# Angle-Sensor_V1_0.net
KiCad netlist of a schematic drawn in Altium Designer
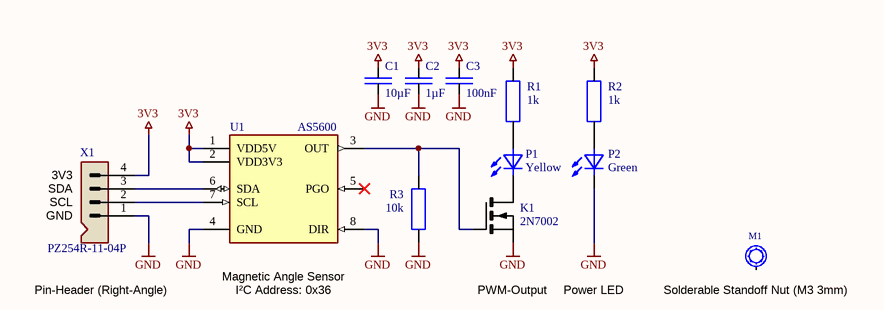
[diagram p0: Angle-Sensor_V1.0.SchDoc]

(export (version "E")
  (design (tool "Eeschema 10.0.6"))
  (components
    (comp (ref "C1")
      (value "10µF")
      (footprint "SMD Keramikkondensator 1206")
      (description "SMD Ceramic Capacitor E6")
      (libsource (lib "Ceramic Capacitors-E6") (part "E6 - 10uF"))
    )
    (comp (ref "C2")
      (value "1µF")
      (footprint "SMD Keramikkondensator 0603")
      (description "CAP-MK")
      (libsource (lib "AudioAmp") (part "C-CAPACITOR"))
    )
    (comp (ref "C3")
      (value "100nF")
      (footprint "SMD Keramikkondensator 0603")
      (description "SMD Ceramic Capacitor E6")
      (libsource (lib "Ceramic Capacitors-E6") (part "E6 - 100nF"))
    )
    (comp (ref "K1")
      (value "2N7002")
      (footprint "SMD MOSFET SOT-23")
      (description "MOSFET N-Channel")
      (libsource (lib "Nixie-Test") (part "K-FET{colon}NIGE"))
    )
    (comp (ref "M1")
      (value "SMTSO-M3-3ET")
      (footprint "SMD Solder-Nut (M3 3mm)")
      (description "Solderable Standoff Nut")
      (libsource (lib "Velotour_2022") (part "M-Spacer_M3_3mm"))
    )
    (comp (ref "P1")
      (value "Yellow")
      (footprint "SMD LED 0603")
      (description "LED (als Lampe E / alt H)")
      (libsource (lib "TFS Integrated Library") (part "P-LED"))
    )
    (comp (ref "P2")
      (value "Green")
      (footprint "SMD LED 0603")
      (description "General Purpose LED")
      (libsource (lib "Fleet-Monitor") (part "LED Green 0603"))
    )
    (comp (ref "R1")
      (value "1k")
      (footprint "SMD Widerstand 0603")
      (description "RES (E=Heizwiderstand B=Messwandler)")
      (libsource (lib "TFS Integrated Library") (part "R-RESISTOR"))
    )
    (comp (ref "R2")
      (value "1k")
      (footprint "SMD Widerstand 0603")
      (description "RES (E=Heizwiderstand B=Messwandler)")
      (libsource (lib "TFS Integrated Library") (part "R-RESISTOR"))
    )
    (comp (ref "R3")
      (value "10k")
      (footprint "SMD Widerstand 0603")
      (description "RES (E=Heizwiderstand B=Messwandler)")
      (libsource (lib "TFS Integrated Library") (part "R-RESISTOR"))
    )
    (comp (ref "U1")
      (value "AS5600")
      (footprint "SMD IC SOIC-8")
      (description "Digital Magnetic Angle Sensor")
      (libsource (lib "Angle-Sensor") (part "U-AS5600"))
    )
    (comp (ref "X1")
      (value "PZ254R-11-04P")
      (footprint "THT Pin-Header 4x1 (90°)")
      (description "Pin Header (Right-Angle)")
      (libsource (lib "Angle-Sensor") (part "X-Stiftleiste (4-Fach, Right-Angle)"))
    )
  )
  (nets
    (net (code "1") (name "3V3") (class "Default")
      (node (ref "C1") (pin "2") (pinfunction "2_2") (pintype "passive"))
      (node (ref "C2") (pin "2") (pinfunction "2_2") (pintype "passive"))
      (node (ref "C3") (pin "1") (pinfunction "1_1") (pintype "passive"))
      (node (ref "R1") (pin "2") (pinfunction "2_2") (pintype "passive"))
      (node (ref "R2") (pin "2") (pinfunction "2_2") (pintype "passive"))
      (node (ref "U1") (pin "1") (pinfunction "VDD5V_1") (pintype "power_in"))
      (node (ref "U1") (pin "2") (pinfunction "VDD3V3_2") (pintype "power_in"))
      (node (ref "X1") (pin "4") (pinfunction "4_4") (pintype "passive"))
    )
    (net (code "2") (name "GND") (class "Default")
      (node (ref "C1") (pin "1") (pinfunction "1_1") (pintype "passive"))
      (node (ref "C2") (pin "1") (pinfunction "1_1") (pintype "passive"))
      (node (ref "C3") (pin "2") (pinfunction "2_2") (pintype "passive"))
      (node (ref "K1") (pin "S") (pinfunction "S_S") (pintype "passive"))
      (node (ref "P2") (pin "K") (pinfunction "K_K") (pintype "passive"))
      (node (ref "R3") (pin "1") (pinfunction "1_1") (pintype "passive"))
      (node (ref "U1") (pin "4") (pinfunction "GND_4") (pintype "power_in"))
      (node (ref "U1") (pin "8") (pinfunction "DIR_8") (pintype "input"))
      (node (ref "X1") (pin "1") (pinfunction "1_1") (pintype "passive"))
    )
    (net (code "3") (name "Net-(K1-PadD)") (class "Default")
      (node (ref "K1") (pin "D") (pinfunction "D_D") (pintype "passive"))
      (node (ref "P1") (pin "K") (pinfunction "K_K") (pintype "passive"))
    )
    (net (code "4") (name "Net-(P1-PadA)") (class "Default")
      (node (ref "P1") (pin "A") (pinfunction "A_A") (pintype "passive"))
      (node (ref "R1") (pin "1") (pinfunction "1_1") (pintype "passive"))
    )
    (net (code "5") (name "Net-(P2-PadA)") (class "Default")
      (node (ref "P2") (pin "A") (pinfunction "A_A") (pintype "passive"))
      (node (ref "R2") (pin "1") (pinfunction "1_1") (pintype "passive"))
    )
    (net (code "6") (name "Net-(U1-OUT)") (class "Default")
      (node (ref "K1") (pin "G") (pinfunction "G_G") (pintype "passive"))
      (node (ref "R3") (pin "2") (pinfunction "2_2") (pintype "passive"))
      (node (ref "U1") (pin "3") (pinfunction "OUT_3") (pintype "output"))
    )
    (net (code "7") (name "Net-(U1-SCL)") (class "Default")
      (node (ref "U1") (pin "7") (pinfunction "SCL_7") (pintype "input"))
      (node (ref "X1") (pin "2") (pinfunction "2_2") (pintype "passive"))
    )
    (net (code "8") (name "Net-(U1-SDA)") (class "Default")
      (node (ref "U1") (pin "6") (pinfunction "SDA_6") (pintype "bidirectional"))
      (node (ref "X1") (pin "3") (pinfunction "3_3") (pintype "passive"))
    )
    (net (code "9") (name "unconnected-(M1-Pad1)") (class "Default")
      (node (ref "M1") (pin "1") (pinfunction "1_1") (pintype "passive"))
    )
    (net (code "10") (name "unconnected-(U1-PGO-Pad5)") (class "Default")
      (node (ref "U1") (pin "5") (pinfunction "PGO_5") (pintype "input+no_connect"))
    )
  )
)
